# SW_RESET_SPNO.net
KiCad netlist of a schematic drawn in Altium Designer
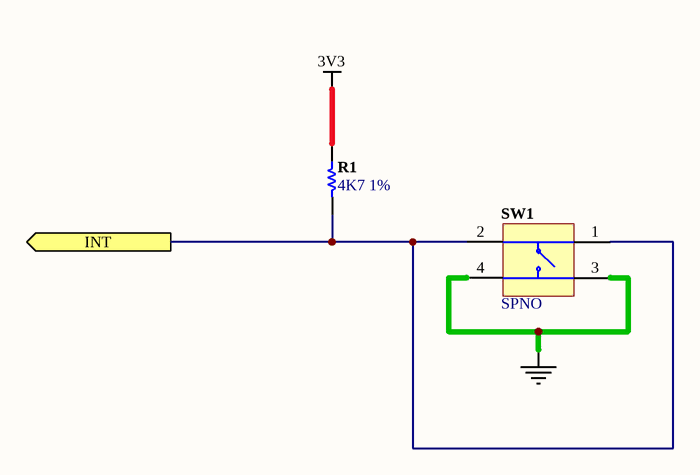
[diagram p0: SW_RESET_SPNO.SCHDOC]

(export (version "E")
  (design (tool "Eeschema 10.0.6"))
  (components
    (comp (ref "R1")
      (value "4K7 1%")
      (footprint "RESC1005-STAR")
      (description "Resistor, 4K7 1% 0402 (1005)")
      (fields (field (name "TOLERANCE") "1 %"))
      (libsource (lib "altium-import") (part "root_0_mirrored_RES_"))
    )
    (comp (ref "SW1")
      (value "SPNO")
      (footprint "SW_DTSM-61NT/R")
      (description "Switch, SPNO Push Button SMD")
      (libsource (lib "AltiumDesignLibrary") (part "SWI-PB-SPNO"))
    )
  )
  (nets
    (net (code "1") (name "/INT") (class "Default")
      (node (ref "R1") (pin "2") (pinfunction "2_2") (pintype "passive"))
      (node (ref "SW1") (pin "1") (pinfunction "1_1") (pintype "passive"))
      (node (ref "SW1") (pin "2") (pinfunction "2_2") (pintype "passive"))
    )
    (net (code "2") (name "3V3") (class "Default")
      (node (ref "R1") (pin "1") (pinfunction "1_1") (pintype "passive"))
    )
    (net (code "3") (name "GND") (class "Default")
      (node (ref "SW1") (pin "3") (pinfunction "3_3") (pintype "passive"))
      (node (ref "SW1") (pin "4") (pinfunction "4_4") (pintype "passive"))
    )
  )
)
